# segment_display_2x_static.net
KiCad netlist of a schematic drawn in EAGLE
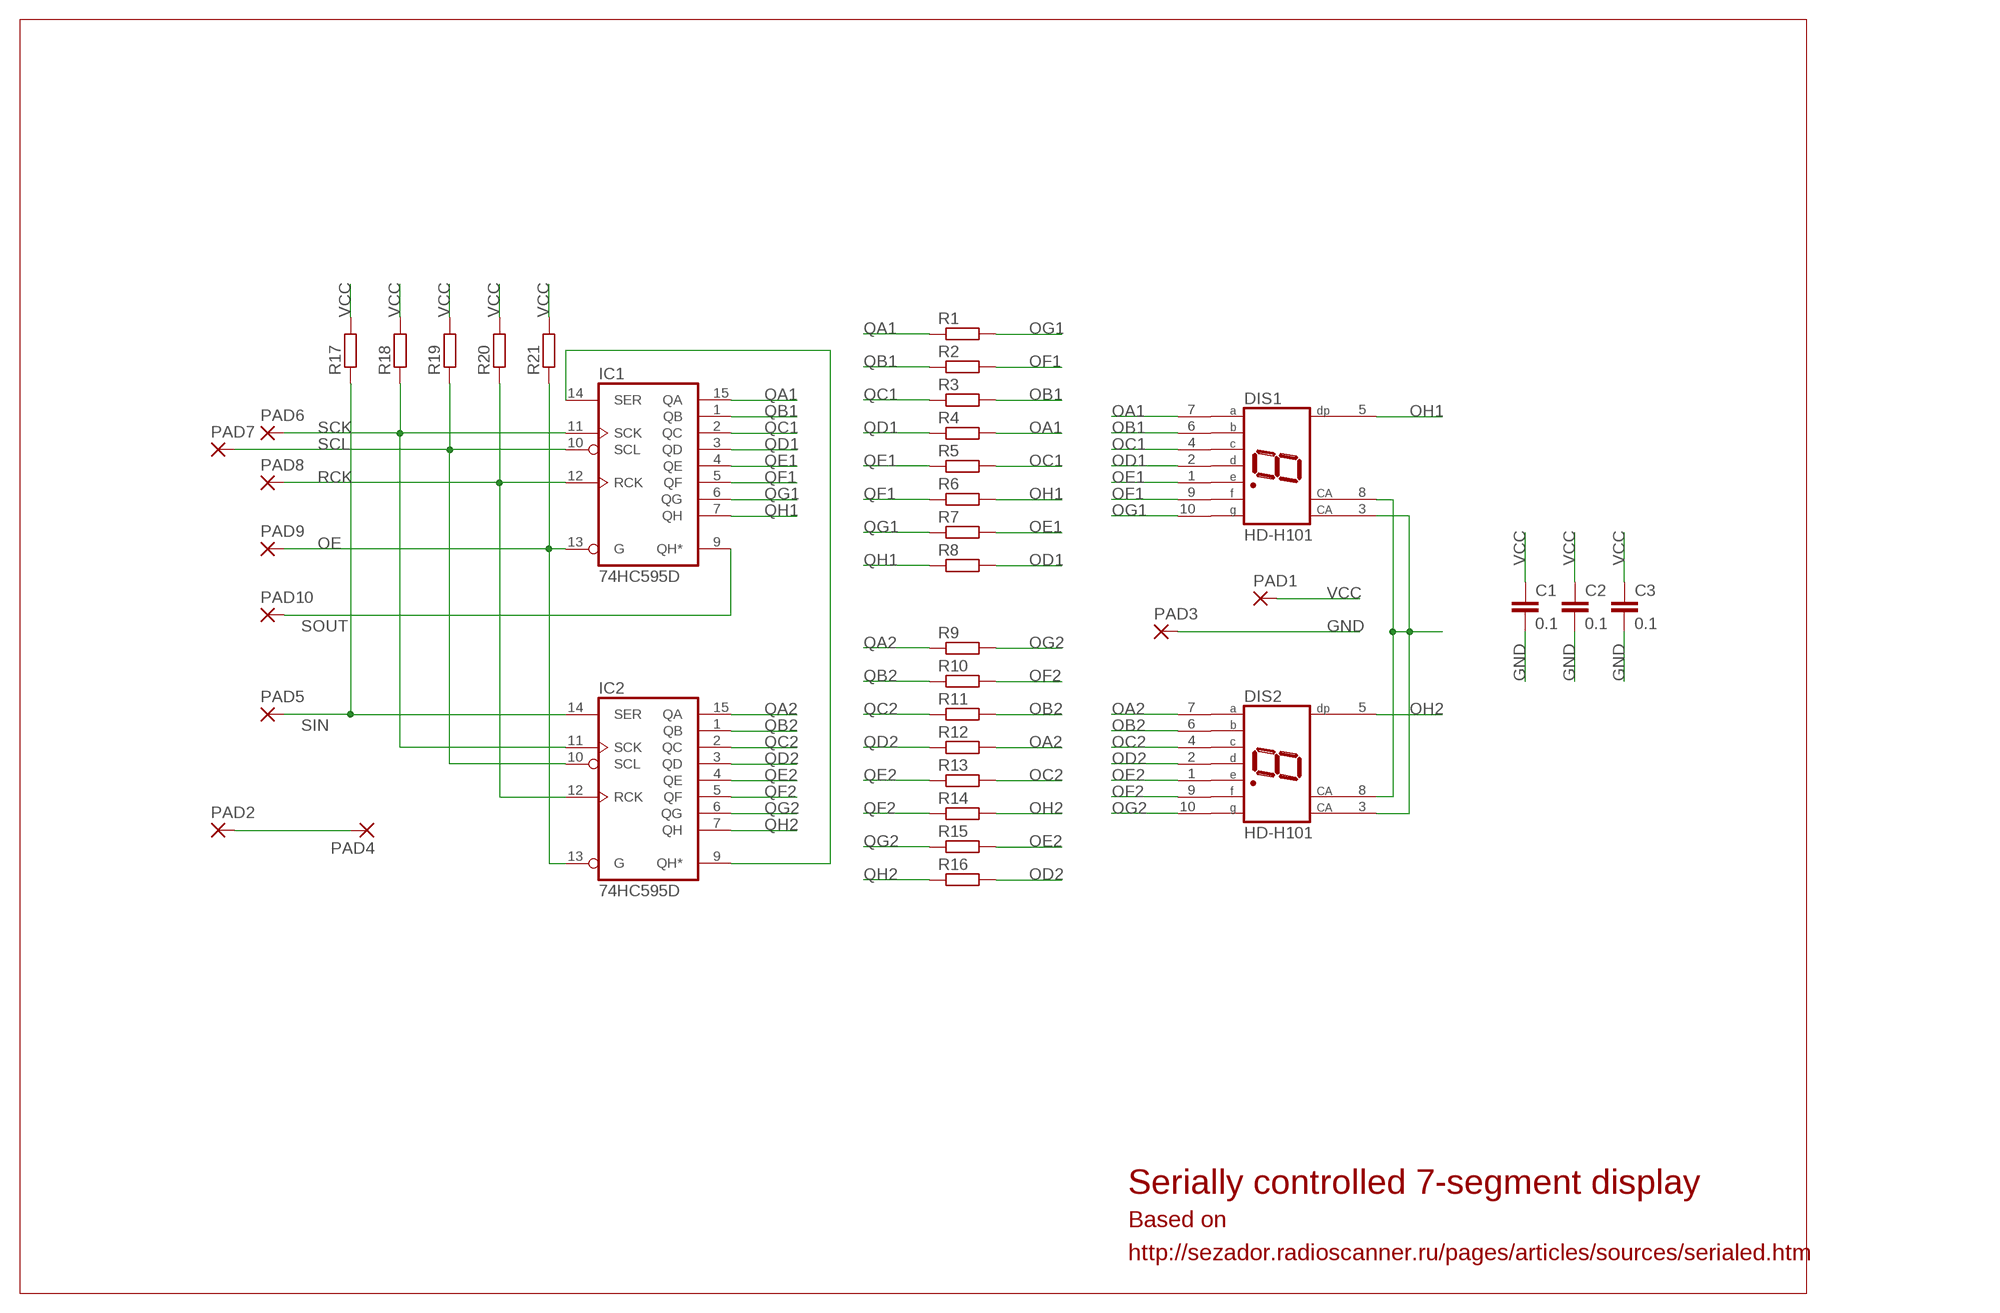
[diagram p0: schematic, sheet 1]

(export (version "E")
  (design (tool "Eeschema 10.0.6"))
  (components
    (comp (ref "C1")
      (value "0.1")
      (footprint "eagle-import:C0805")
      (libsource (lib "eagle-import") (part "C-EUC0805"))
    )
    (comp (ref "C2")
      (value "0.1")
      (footprint "eagle-import:C0805")
      (libsource (lib "eagle-import") (part "C-EUC0805"))
    )
    (comp (ref "C3")
      (value "0.1")
      (footprint "eagle-import:C0805")
      (libsource (lib "eagle-import") (part "C-EUC0805"))
    )
    (comp (ref "DIS1")
      (value "HD-H101")
      (footprint "eagle-import:HDSP-M")
      (libsource (lib "eagle-import") (part "HD-H101"))
    )
    (comp (ref "DIS2")
      (value "HD-H101")
      (footprint "eagle-import:HDSP-M")
      (libsource (lib "eagle-import") (part "HD-H101"))
    )
    (comp (ref "IC1")
      (value "74HC595D")
      (footprint "eagle-import:SO16")
      (libsource (lib "eagle-import") (part "74595DHC"))
    )
    (comp (ref "IC2")
      (value "74HC595D")
      (footprint "eagle-import:SO16")
      (libsource (lib "eagle-import") (part "74595DHC"))
    )
    (comp (ref "PAD1")
      (value "1,6/0,8")
      (footprint "eagle-import:1,6_0,8")
      (libsource (lib "eagle-import") (part "1,6/0,8"))
    )
    (comp (ref "PAD2")
      (value "1,6/0,8")
      (footprint "eagle-import:1,6_0,8")
      (libsource (lib "eagle-import") (part "1,6/0,8"))
    )
    (comp (ref "PAD3")
      (value "1,6/0,8")
      (footprint "eagle-import:1,6_0,8")
      (libsource (lib "eagle-import") (part "1,6/0,8"))
    )
    (comp (ref "PAD4")
      (value "1,6/0,8")
      (footprint "eagle-import:1,6_0,8")
      (libsource (lib "eagle-import") (part "1,6/0,8"))
    )
    (comp (ref "PAD5")
      (value "1,6/0,8")
      (footprint "eagle-import:1,6_0,8")
      (libsource (lib "eagle-import") (part "1,6/0,8"))
    )
    (comp (ref "PAD6")
      (value "1,6/0,8")
      (footprint "eagle-import:1,6_0,8")
      (libsource (lib "eagle-import") (part "1,6/0,8"))
    )
    (comp (ref "PAD7")
      (value "1,6/0,8")
      (footprint "eagle-import:1,6_0,8")
      (libsource (lib "eagle-import") (part "1,6/0,8"))
    )
    (comp (ref "PAD8")
      (value "1,6/0,8")
      (footprint "eagle-import:1,6_0,8")
      (libsource (lib "eagle-import") (part "1,6/0,8"))
    )
    (comp (ref "PAD9")
      (value "1,6/0,8")
      (footprint "eagle-import:1,6_0,8")
      (libsource (lib "eagle-import") (part "1,6/0,8"))
    )
    (comp (ref "PAD10")
      (value "1,6/0,8")
      (footprint "eagle-import:1,6_0,8")
      (libsource (lib "eagle-import") (part "1,6/0,8"))
    )
    (comp (ref "R1")
      (value "R-EU_R0805")
      (footprint "eagle-import:R0805")
      (libsource (lib "eagle-import") (part "R-EU_R0805"))
    )
    (comp (ref "R2")
      (value "R-EU_R0805")
      (footprint "eagle-import:R0805")
      (libsource (lib "eagle-import") (part "R-EU_R0805"))
    )
    (comp (ref "R3")
      (value "R-EU_R0805")
      (footprint "eagle-import:R0805")
      (libsource (lib "eagle-import") (part "R-EU_R0805"))
    )
    (comp (ref "R4")
      (value "R-EU_R0805")
      (footprint "eagle-import:R0805")
      (libsource (lib "eagle-import") (part "R-EU_R0805"))
    )
    (comp (ref "R5")
      (value "R-EU_R0805")
      (footprint "eagle-import:R0805")
      (libsource (lib "eagle-import") (part "R-EU_R0805"))
    )
    (comp (ref "R6")
      (value "R-EU_R0805")
      (footprint "eagle-import:R0805")
      (libsource (lib "eagle-import") (part "R-EU_R0805"))
    )
    (comp (ref "R7")
      (value "R-EU_R0805")
      (footprint "eagle-import:R0805")
      (libsource (lib "eagle-import") (part "R-EU_R0805"))
    )
    (comp (ref "R8")
      (value "R-EU_R0805")
      (footprint "eagle-import:R0805")
      (libsource (lib "eagle-import") (part "R-EU_R0805"))
    )
    (comp (ref "R9")
      (value "R-EU_R0805")
      (footprint "eagle-import:R0805")
      (libsource (lib "eagle-import") (part "R-EU_R0805"))
    )
    (comp (ref "R10")
      (value "R-EU_R0805")
      (footprint "eagle-import:R0805")
      (libsource (lib "eagle-import") (part "R-EU_R0805"))
    )
    (comp (ref "R11")
      (value "R-EU_R0805")
      (footprint "eagle-import:R0805")
      (libsource (lib "eagle-import") (part "R-EU_R0805"))
    )
    (comp (ref "R12")
      (value "R-EU_R0805")
      (footprint "eagle-import:R0805")
      (libsource (lib "eagle-import") (part "R-EU_R0805"))
    )
    (comp (ref "R13")
      (value "R-EU_R0805")
      (footprint "eagle-import:R0805")
      (libsource (lib "eagle-import") (part "R-EU_R0805"))
    )
    (comp (ref "R14")
      (value "R-EU_R0805")
      (footprint "eagle-import:R0805")
      (libsource (lib "eagle-import") (part "R-EU_R0805"))
    )
    (comp (ref "R15")
      (value "R-EU_R0805")
      (footprint "eagle-import:R0805")
      (libsource (lib "eagle-import") (part "R-EU_R0805"))
    )
    (comp (ref "R16")
      (value "R-EU_R0805")
      (footprint "eagle-import:R0805")
      (libsource (lib "eagle-import") (part "R-EU_R0805"))
    )
    (comp (ref "R17")
      (value "R-EU_R0805")
      (footprint "eagle-import:R0805")
      (libsource (lib "eagle-import") (part "R-EU_R0805"))
    )
    (comp (ref "R18")
      (value "R-EU_R0805")
      (footprint "eagle-import:R0805")
      (libsource (lib "eagle-import") (part "R-EU_R0805"))
    )
    (comp (ref "R19")
      (value "R-EU_R0805")
      (footprint "eagle-import:R0805")
      (libsource (lib "eagle-import") (part "R-EU_R0805"))
    )
    (comp (ref "R20")
      (value "R-EU_R0805")
      (footprint "eagle-import:R0805")
      (libsource (lib "eagle-import") (part "R-EU_R0805"))
    )
    (comp (ref "R21")
      (value "R-EU_R0805")
      (footprint "eagle-import:R0805")
      (libsource (lib "eagle-import") (part "R-EU_R0805"))
    )
  )
  (nets
    (net (code "1") (name "/GND") (class "Default")
      (node (ref "C1") (pin "2") (pinfunction "2_2") (pintype "passive"))
      (node (ref "C2") (pin "2") (pinfunction "2_2") (pintype "passive"))
      (node (ref "C3") (pin "2") (pinfunction "2_2") (pintype "passive"))
      (node (ref "PAD3") (pin "1") (pinfunction "P_1") (pintype "passive"))
    )
    (net (code "2") (name "/OA1") (class "Default")
      (node (ref "DIS1") (pin "7") (pinfunction "A_7") (pintype "passive"))
      (node (ref "R4") (pin "2") (pinfunction "2_2") (pintype "passive"))
    )
    (net (code "3") (name "/OA2") (class "Default")
      (node (ref "DIS2") (pin "7") (pinfunction "A_7") (pintype "passive"))
      (node (ref "R12") (pin "2") (pinfunction "2_2") (pintype "passive"))
    )
    (net (code "4") (name "/OB1") (class "Default")
      (node (ref "DIS1") (pin "6") (pinfunction "B_6") (pintype "passive"))
      (node (ref "R3") (pin "2") (pinfunction "2_2") (pintype "passive"))
    )
    (net (code "5") (name "/OB2") (class "Default")
      (node (ref "DIS2") (pin "6") (pinfunction "B_6") (pintype "passive"))
      (node (ref "R11") (pin "2") (pinfunction "2_2") (pintype "passive"))
    )
    (net (code "6") (name "/OC1") (class "Default")
      (node (ref "DIS1") (pin "4") (pinfunction "C_4") (pintype "passive"))
      (node (ref "R5") (pin "2") (pinfunction "2_2") (pintype "passive"))
    )
    (net (code "7") (name "/OC2") (class "Default")
      (node (ref "DIS2") (pin "4") (pinfunction "C_4") (pintype "passive"))
      (node (ref "R13") (pin "2") (pinfunction "2_2") (pintype "passive"))
    )
    (net (code "8") (name "/OD1") (class "Default")
      (node (ref "DIS1") (pin "2") (pinfunction "D_2") (pintype "passive"))
      (node (ref "R8") (pin "2") (pinfunction "2_2") (pintype "passive"))
    )
    (net (code "9") (name "/OD2") (class "Default")
      (node (ref "DIS2") (pin "2") (pinfunction "D_2") (pintype "passive"))
      (node (ref "R16") (pin "2") (pinfunction "2_2") (pintype "passive"))
    )
    (net (code "10") (name "/OE") (class "Default")
      (node (ref "IC1") (pin "13") (pinfunction "G_13") (pintype "input"))
      (node (ref "IC2") (pin "13") (pinfunction "G_13") (pintype "input"))
      (node (ref "PAD9") (pin "1") (pinfunction "P_1") (pintype "passive"))
      (node (ref "R21") (pin "1") (pinfunction "1_1") (pintype "passive"))
    )
    (net (code "11") (name "/OE1") (class "Default")
      (node (ref "DIS1") (pin "1") (pinfunction "E_1") (pintype "passive"))
      (node (ref "R7") (pin "2") (pinfunction "2_2") (pintype "passive"))
    )
    (net (code "12") (name "/OE2") (class "Default")
      (node (ref "DIS2") (pin "1") (pinfunction "E_1") (pintype "passive"))
      (node (ref "R15") (pin "2") (pinfunction "2_2") (pintype "passive"))
    )
    (net (code "13") (name "/OF1") (class "Default")
      (node (ref "DIS1") (pin "9") (pinfunction "F_9") (pintype "passive"))
      (node (ref "R2") (pin "2") (pinfunction "2_2") (pintype "passive"))
    )
    (net (code "14") (name "/OF2") (class "Default")
      (node (ref "DIS2") (pin "9") (pinfunction "F_9") (pintype "passive"))
      (node (ref "R10") (pin "2") (pinfunction "2_2") (pintype "passive"))
    )
    (net (code "15") (name "/OG1") (class "Default")
      (node (ref "DIS1") (pin "10") (pinfunction "G_10") (pintype "passive"))
      (node (ref "R1") (pin "2") (pinfunction "2_2") (pintype "passive"))
    )
    (net (code "16") (name "/OG2") (class "Default")
      (node (ref "DIS2") (pin "10") (pinfunction "G_10") (pintype "passive"))
      (node (ref "R9") (pin "2") (pinfunction "2_2") (pintype "passive"))
    )
    (net (code "17") (name "/OH1") (class "Default")
      (node (ref "DIS1") (pin "5") (pinfunction "DP_5") (pintype "passive"))
      (node (ref "R6") (pin "2") (pinfunction "2_2") (pintype "passive"))
    )
    (net (code "18") (name "/OH2") (class "Default")
      (node (ref "DIS2") (pin "5") (pinfunction "DP_5") (pintype "passive"))
      (node (ref "R14") (pin "2") (pinfunction "2_2") (pintype "passive"))
    )
    (net (code "19") (name "/QA1") (class "Default")
      (node (ref "IC1") (pin "15") (pinfunction "QA_15") (pintype "tri_state"))
      (node (ref "R1") (pin "1") (pinfunction "1_1") (pintype "passive"))
    )
    (net (code "20") (name "/QA2") (class "Default")
      (node (ref "IC2") (pin "15") (pinfunction "QA_15") (pintype "tri_state"))
      (node (ref "R9") (pin "1") (pinfunction "1_1") (pintype "passive"))
    )
    (net (code "21") (name "/QB1") (class "Default")
      (node (ref "IC1") (pin "1") (pinfunction "QB_1") (pintype "tri_state"))
      (node (ref "R2") (pin "1") (pinfunction "1_1") (pintype "passive"))
    )
    (net (code "22") (name "/QB2") (class "Default")
      (node (ref "IC2") (pin "1") (pinfunction "QB_1") (pintype "tri_state"))
      (node (ref "R10") (pin "1") (pinfunction "1_1") (pintype "passive"))
    )
    (net (code "23") (name "/QC1") (class "Default")
      (node (ref "IC1") (pin "2") (pinfunction "QC_2") (pintype "tri_state"))
      (node (ref "R3") (pin "1") (pinfunction "1_1") (pintype "passive"))
    )
    (net (code "24") (name "/QC2") (class "Default")
      (node (ref "IC2") (pin "2") (pinfunction "QC_2") (pintype "tri_state"))
      (node (ref "R11") (pin "1") (pinfunction "1_1") (pintype "passive"))
    )
    (net (code "25") (name "/QD1") (class "Default")
      (node (ref "IC1") (pin "3") (pinfunction "QD_3") (pintype "tri_state"))
      (node (ref "R4") (pin "1") (pinfunction "1_1") (pintype "passive"))
    )
    (net (code "26") (name "/QD2") (class "Default")
      (node (ref "IC2") (pin "3") (pinfunction "QD_3") (pintype "tri_state"))
      (node (ref "R12") (pin "1") (pinfunction "1_1") (pintype "passive"))
    )
    (net (code "27") (name "/QE1") (class "Default")
      (node (ref "IC1") (pin "4") (pinfunction "QE_4") (pintype "tri_state"))
      (node (ref "R5") (pin "1") (pinfunction "1_1") (pintype "passive"))
    )
    (net (code "28") (name "/QE2") (class "Default")
      (node (ref "IC2") (pin "4") (pinfunction "QE_4") (pintype "tri_state"))
      (node (ref "R13") (pin "1") (pinfunction "1_1") (pintype "passive"))
    )
    (net (code "29") (name "/QF1") (class "Default")
      (node (ref "IC1") (pin "5") (pinfunction "QF_5") (pintype "tri_state"))
      (node (ref "R6") (pin "1") (pinfunction "1_1") (pintype "passive"))
    )
    (net (code "30") (name "/QF2") (class "Default")
      (node (ref "IC2") (pin "5") (pinfunction "QF_5") (pintype "tri_state"))
      (node (ref "R14") (pin "1") (pinfunction "1_1") (pintype "passive"))
    )
    (net (code "31") (name "/QG1") (class "Default")
      (node (ref "IC1") (pin "6") (pinfunction "QG_6") (pintype "tri_state"))
      (node (ref "R7") (pin "1") (pinfunction "1_1") (pintype "passive"))
    )
    (net (code "32") (name "/QG2") (class "Default")
      (node (ref "IC2") (pin "6") (pinfunction "QG_6") (pintype "tri_state"))
      (node (ref "R15") (pin "1") (pinfunction "1_1") (pintype "passive"))
    )
    (net (code "33") (name "/QH1") (class "Default")
      (node (ref "IC1") (pin "7") (pinfunction "QH_7") (pintype "tri_state"))
      (node (ref "R8") (pin "1") (pinfunction "1_1") (pintype "passive"))
    )
    (net (code "34") (name "/QH2") (class "Default")
      (node (ref "IC2") (pin "7") (pinfunction "QH_7") (pintype "tri_state"))
      (node (ref "R16") (pin "1") (pinfunction "1_1") (pintype "passive"))
    )
    (net (code "35") (name "/RCK") (class "Default")
      (node (ref "IC1") (pin "12") (pinfunction "RCK_12") (pintype "input"))
      (node (ref "IC2") (pin "12") (pinfunction "RCK_12") (pintype "input"))
      (node (ref "PAD8") (pin "1") (pinfunction "P_1") (pintype "passive"))
      (node (ref "R20") (pin "1") (pinfunction "1_1") (pintype "passive"))
    )
    (net (code "36") (name "/SCK") (class "Default")
      (node (ref "IC1") (pin "11") (pinfunction "SCK_11") (pintype "input"))
      (node (ref "IC2") (pin "11") (pinfunction "SCK_11") (pintype "input"))
      (node (ref "PAD6") (pin "1") (pinfunction "P_1") (pintype "passive"))
      (node (ref "R18") (pin "1") (pinfunction "1_1") (pintype "passive"))
    )
    (net (code "37") (name "/SCL") (class "Default")
      (node (ref "IC1") (pin "10") (pinfunction "SCL_10") (pintype "input"))
      (node (ref "IC2") (pin "10") (pinfunction "SCL_10") (pintype "input"))
      (node (ref "PAD7") (pin "1") (pinfunction "P_1") (pintype "passive"))
      (node (ref "R19") (pin "1") (pinfunction "1_1") (pintype "passive"))
    )
    (net (code "38") (name "/SIN") (class "Default")
      (node (ref "IC2") (pin "14") (pinfunction "SER_14") (pintype "input"))
      (node (ref "PAD5") (pin "1") (pinfunction "P_1") (pintype "passive"))
      (node (ref "R17") (pin "1") (pinfunction "1_1") (pintype "passive"))
    )
    (net (code "39") (name "/SOUT") (class "Default")
      (node (ref "IC1") (pin "9") (pinfunction "QH*_9") (pintype "tri_state"))
      (node (ref "PAD10") (pin "1") (pinfunction "P_1") (pintype "passive"))
    )
    (net (code "40") (name "/VCC") (class "Default")
      (node (ref "C1") (pin "1") (pinfunction "1_1") (pintype "passive"))
      (node (ref "C2") (pin "1") (pinfunction "1_1") (pintype "passive"))
      (node (ref "C3") (pin "1") (pinfunction "1_1") (pintype "passive"))
      (node (ref "DIS1") (pin "3") (pinfunction "CA_3") (pintype "passive"))
      (node (ref "DIS1") (pin "8") (pinfunction "CA_8") (pintype "passive"))
      (node (ref "DIS2") (pin "3") (pinfunction "CA_3") (pintype "passive"))
      (node (ref "DIS2") (pin "8") (pinfunction "CA_8") (pintype "passive"))
      (node (ref "PAD1") (pin "1") (pinfunction "P_1") (pintype "passive"))
      (node (ref "R17") (pin "2") (pinfunction "2_2") (pintype "passive"))
      (node (ref "R18") (pin "2") (pinfunction "2_2") (pintype "passive"))
      (node (ref "R19") (pin "2") (pinfunction "2_2") (pintype "passive"))
      (node (ref "R20") (pin "2") (pinfunction "2_2") (pintype "passive"))
      (node (ref "R21") (pin "2") (pinfunction "2_2") (pintype "passive"))
    )
    (net (code "41") (name "Net-(IC1A-SER)") (class "Default")
      (node (ref "IC1") (pin "14") (pinfunction "SER_14") (pintype "input"))
      (node (ref "IC2") (pin "9") (pinfunction "QH*_9") (pintype "tri_state"))
    )
    (net (code "42") (name "Net-(PAD2-P)") (class "Default")
      (node (ref "PAD2") (pin "1") (pinfunction "P_1") (pintype "passive"))
      (node (ref "PAD4") (pin "1") (pinfunction "P_1") (pintype "passive"))
    )
  )
)
